# H_Bridge.net
KiCad netlist of a schematic drawn in Altium Designer
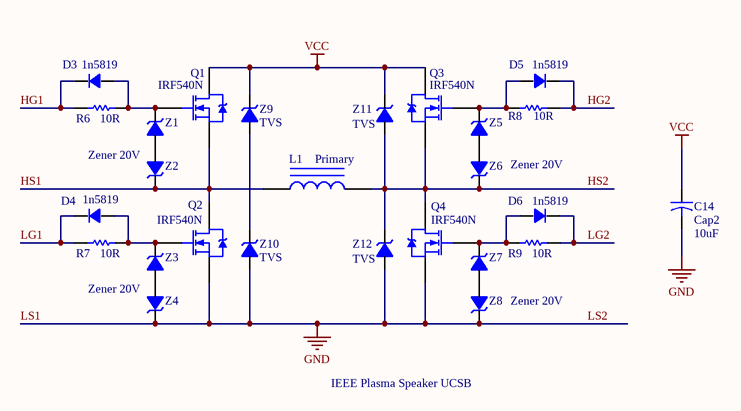
[diagram p0: H Bridge.SchDoc]

(export (version "E")
  (design (tool "Eeschema 10.0.6"))
  (components
    (comp (ref "C14")
      (value "Cap2")
      (footprint "CAPR5-4X5")
      (description "Capacitor")
      (fields (field (name "ALTIUM_VALUE") "10uF") (field (name "PUBLISHER") "Altium Limited"))
      (libsource (lib "Miscellaneous Devices") (part "Cap2"))
    )
    (comp (ref "D3")
      (value "1n5819")
      (footprint "DIODE-0.7")
      (description "Zener Diode")
      (fields (field (name "PUBLISHER") "Altium Limited"))
      (libsource (lib "Miscellaneous Devices") (part "Diode S"))
    )
    (comp (ref "D4")
      (value "1n5819")
      (footprint "DIODE-0.7")
      (description "Zener Diode")
      (fields (field (name "PUBLISHER") "Altium Limited"))
      (libsource (lib "Miscellaneous Devices") (part "Diode S"))
    )
    (comp (ref "D5")
      (value "1n5819")
      (footprint "DIODE-0.7")
      (description "Zener Diode")
      (fields (field (name "PUBLISHER") "Altium Limited"))
      (libsource (lib "Miscellaneous Devices") (part "Diode S"))
    )
    (comp (ref "D6")
      (value "1n5819")
      (footprint "DIODE-0.7")
      (description "Zener Diode")
      (fields (field (name "PUBLISHER") "Altium Limited"))
      (libsource (lib "Miscellaneous Devices") (part "Diode S"))
    )
    (comp (ref "L1")
      (value "Primary")
      (footprint "AXIAL-0.9")
      (description "Magnetic-Core Inductor")
      (fields (field (name "Comment") "Inductor Iron") (field (name "PUBLISHER") "Altium Limited"))
      (libsource (lib "Miscellaneous Devices") (part "Inductor Iron"))
    )
    (comp (ref "Q1")
      (value "IRF540N")
      (footprint "TO-220AB")
      (description "N-Channel Power MOSFET")
      (fields (field (name "PUBLISHER") "Altium Limited"))
      (libsource (lib "Transistor") (part "IRF540N"))
    )
    (comp (ref "Q2")
      (value "IRF540N")
      (footprint "TO-220AB")
      (description "N-Channel Power MOSFET")
      (fields (field (name "PUBLISHER") "Altium Limited"))
      (libsource (lib "Transistor") (part "IRF540N"))
    )
    (comp (ref "Q3")
      (value "IRF540N")
      (footprint "TO-220AB")
      (description "N-Channel Power MOSFET")
      (fields (field (name "PUBLISHER") "Altium Limited"))
      (libsource (lib "Transistor") (part "IRF540N"))
    )
    (comp (ref "Q4")
      (value "IRF540N")
      (footprint "TO-220AB")
      (description "N-Channel Power MOSFET")
      (fields (field (name "PUBLISHER") "Altium Limited"))
      (libsource (lib "Transistor") (part "IRF540N"))
    )
    (comp (ref "R6")
      (value "10R")
      (footprint "AXIAL-0.3")
      (description "Resistor")
      (fields (field (name "Comment") "0805") (field (name "PUBLISHER") "Altium Limited"))
      (libsource (lib "Miscellaneous Devices") (part "Res1"))
    )
    (comp (ref "R7")
      (value "10R")
      (footprint "AXIAL-0.3")
      (description "Resistor")
      (fields (field (name "Comment") "0805") (field (name "PUBLISHER") "Altium Limited"))
      (libsource (lib "Miscellaneous Devices") (part "Res1"))
    )
    (comp (ref "R8")
      (value "10R")
      (footprint "AXIAL-0.3")
      (description "Resistor")
      (fields (field (name "Comment") "0805") (field (name "PUBLISHER") "Altium Limited"))
      (libsource (lib "Miscellaneous Devices") (part "Res1"))
    )
    (comp (ref "R9")
      (value "10R")
      (footprint "AXIAL-0.3")
      (description "Resistor")
      (fields (field (name "Comment") "0805") (field (name "PUBLISHER") "Altium Limited"))
      (libsource (lib "Miscellaneous Devices") (part "Res1"))
    )
    (comp (ref "Z1")
      (value "Zener 20V")
      (footprint "DIODE-0.7")
      (description "Zener Diode")
      (fields (field (name "PUBLISHER") "Altium Limited"))
      (libsource (lib "Miscellaneous Devices") (part "Zener"))
    )
    (comp (ref "Z2")
      (value "Zener")
      (footprint "DIODE-0.7")
      (description "Zener Diode")
      (fields (field (name "PUBLISHER") "Altium Limited"))
      (libsource (lib "Miscellaneous Devices") (part "Zener"))
    )
    (comp (ref "Z3")
      (value "Zener 20V")
      (footprint "DIODE-0.7")
      (description "Zener Diode")
      (fields (field (name "PUBLISHER") "Altium Limited"))
      (libsource (lib "Miscellaneous Devices") (part "Zener"))
    )
    (comp (ref "Z4")
      (value "Zener")
      (footprint "DIODE-0.7")
      (description "Zener Diode")
      (fields (field (name "PUBLISHER") "Altium Limited"))
      (libsource (lib "Miscellaneous Devices") (part "Zener"))
    )
    (comp (ref "Z5")
      (value "Zener 20V")
      (footprint "DIODE-0.7")
      (description "Zener Diode")
      (fields (field (name "PUBLISHER") "Altium Limited"))
      (libsource (lib "Miscellaneous Devices") (part "Zener"))
    )
    (comp (ref "Z6")
      (value "Zener")
      (footprint "DIODE-0.7")
      (description "Zener Diode")
      (fields (field (name "PUBLISHER") "Altium Limited"))
      (libsource (lib "Miscellaneous Devices") (part "Zener"))
    )
    (comp (ref "Z7")
      (value "Zener 20V")
      (footprint "DIODE-0.7")
      (description "Zener Diode")
      (fields (field (name "PUBLISHER") "Altium Limited"))
      (libsource (lib "Miscellaneous Devices") (part "Zener"))
    )
    (comp (ref "Z8")
      (value "Zener")
      (footprint "DIODE-0.7")
      (description "Zener Diode")
      (fields (field (name "PUBLISHER") "Altium Limited"))
      (libsource (lib "Miscellaneous Devices") (part "Zener"))
    )
    (comp (ref "Z9")
      (value "TVS")
      (footprint "DIODE-0.7")
      (description "Zener Diode")
      (fields (field (name "PUBLISHER") "Altium Limited"))
      (libsource (lib "Miscellaneous Devices") (part "Zener"))
    )
    (comp (ref "Z10")
      (value "TVS")
      (footprint "DIODE-0.7")
      (description "Zener Diode")
      (fields (field (name "PUBLISHER") "Altium Limited"))
      (libsource (lib "Miscellaneous Devices") (part "Zener"))
    )
    (comp (ref "Z11")
      (value "TVS")
      (footprint "DIODE-0.7")
      (description "Zener Diode")
      (fields (field (name "PUBLISHER") "Altium Limited"))
      (libsource (lib "Miscellaneous Devices") (part "Zener"))
    )
    (comp (ref "Z12")
      (value "TVS")
      (footprint "DIODE-0.7")
      (description "Zener Diode")
      (fields (field (name "PUBLISHER") "Altium Limited"))
      (libsource (lib "Miscellaneous Devices") (part "Zener"))
    )
  )
  (nets
    (net (code "1") (name "/HG1") (class "Default")
      (node (ref "D3") (pin "2") (pinfunction "2_2") (pintype "passive"))
      (node (ref "R6") (pin "2") (pinfunction "2_2") (pintype "passive"))
    )
    (net (code "2") (name "/HG2") (class "Default")
      (node (ref "D5") (pin "2") (pinfunction "2_2") (pintype "passive"))
      (node (ref "R8") (pin "1") (pinfunction "1_1") (pintype "passive"))
    )
    (net (code "3") (name "/HS1") (class "Default")
      (node (ref "L1") (pin "1") (pinfunction "1_1") (pintype "passive"))
      (node (ref "Q1") (pin "3") (pinfunction "S_3") (pintype "passive"))
      (node (ref "Q2") (pin "2") (pinfunction "D_2") (pintype "passive"))
      (node (ref "Z2") (pin "2") (pinfunction "2_2") (pintype "passive"))
    )
    (net (code "4") (name "/HS2") (class "Default")
      (node (ref "L1") (pin "2") (pinfunction "2_2") (pintype "passive"))
      (node (ref "Q3") (pin "3") (pinfunction "S_3") (pintype "passive"))
      (node (ref "Q4") (pin "2") (pinfunction "D_2") (pintype "passive"))
      (node (ref "Z11") (pin "1") (pinfunction "1_1") (pintype "passive"))
      (node (ref "Z12") (pin "2") (pinfunction "2_2") (pintype "passive"))
      (node (ref "Z6") (pin "2") (pinfunction "2_2") (pintype "passive"))
    )
    (net (code "5") (name "/LG1") (class "Default")
      (node (ref "D4") (pin "2") (pinfunction "2_2") (pintype "passive"))
      (node (ref "R7") (pin "2") (pinfunction "2_2") (pintype "passive"))
    )
    (net (code "6") (name "/LG2") (class "Default")
      (node (ref "D6") (pin "2") (pinfunction "2_2") (pintype "passive"))
      (node (ref "R9") (pin "1") (pinfunction "1_1") (pintype "passive"))
    )
    (net (code "7") (name "GND") (class "Default")
      (node (ref "C14") (pin "2") (pinfunction "2_2") (pintype "passive"))
      (node (ref "Q2") (pin "3") (pinfunction "S_3") (pintype "passive"))
      (node (ref "Q4") (pin "3") (pinfunction "S_3") (pintype "passive"))
      (node (ref "Z10") (pin "1") (pinfunction "1_1") (pintype "passive"))
      (node (ref "Z12") (pin "1") (pinfunction "1_1") (pintype "passive"))
      (node (ref "Z4") (pin "2") (pinfunction "2_2") (pintype "passive"))
      (node (ref "Z8") (pin "2") (pinfunction "2_2") (pintype "passive"))
    )
    (net (code "8") (name "Net-(Q1-G)") (class "Default")
      (node (ref "D3") (pin "1") (pinfunction "1_1") (pintype "passive"))
      (node (ref "Q1") (pin "1") (pinfunction "G_1") (pintype "passive"))
      (node (ref "R6") (pin "1") (pinfunction "1_1") (pintype "passive"))
      (node (ref "Z1") (pin "2") (pinfunction "2_2") (pintype "passive"))
    )
    (net (code "9") (name "Net-(Q2-G)") (class "Default")
      (node (ref "D4") (pin "1") (pinfunction "1_1") (pintype "passive"))
      (node (ref "Q2") (pin "1") (pinfunction "G_1") (pintype "passive"))
      (node (ref "R7") (pin "1") (pinfunction "1_1") (pintype "passive"))
      (node (ref "Z3") (pin "2") (pinfunction "2_2") (pintype "passive"))
    )
    (net (code "10") (name "Net-(Q3-G)") (class "Default")
      (node (ref "D5") (pin "1") (pinfunction "1_1") (pintype "passive"))
      (node (ref "Q3") (pin "1") (pinfunction "G_1") (pintype "passive"))
      (node (ref "R8") (pin "2") (pinfunction "2_2") (pintype "passive"))
      (node (ref "Z5") (pin "2") (pinfunction "2_2") (pintype "passive"))
    )
    (net (code "11") (name "Net-(Q4-G)") (class "Default")
      (node (ref "D6") (pin "1") (pinfunction "1_1") (pintype "passive"))
      (node (ref "Q4") (pin "1") (pinfunction "G_1") (pintype "passive"))
      (node (ref "R9") (pin "2") (pinfunction "2_2") (pintype "passive"))
      (node (ref "Z7") (pin "2") (pinfunction "2_2") (pintype "passive"))
    )
    (net (code "12") (name "Net-(Z1-Pad1)") (class "Default")
      (node (ref "Z1") (pin "1") (pinfunction "1_1") (pintype "passive"))
      (node (ref "Z2") (pin "1") (pinfunction "1_1") (pintype "passive"))
    )
    (net (code "13") (name "Net-(Z3-Pad1)") (class "Default")
      (node (ref "Z3") (pin "1") (pinfunction "1_1") (pintype "passive"))
      (node (ref "Z4") (pin "1") (pinfunction "1_1") (pintype "passive"))
    )
    (net (code "14") (name "Net-(Z5-Pad1)") (class "Default")
      (node (ref "Z5") (pin "1") (pinfunction "1_1") (pintype "passive"))
      (node (ref "Z6") (pin "1") (pinfunction "1_1") (pintype "passive"))
    )
    (net (code "15") (name "Net-(Z7-Pad1)") (class "Default")
      (node (ref "Z7") (pin "1") (pinfunction "1_1") (pintype "passive"))
      (node (ref "Z8") (pin "1") (pinfunction "1_1") (pintype "passive"))
    )
    (net (code "16") (name "Net-(Z10-Pad2)") (class "Default")
      (node (ref "Z10") (pin "2") (pinfunction "2_2") (pintype "passive"))
      (node (ref "Z9") (pin "1") (pinfunction "1_1") (pintype "passive"))
    )
    (net (code "17") (name "VCC") (class "Default")
      (node (ref "C14") (pin "1") (pinfunction "1_1") (pintype "passive"))
      (node (ref "Q1") (pin "2") (pinfunction "D_2") (pintype "passive"))
      (node (ref "Q3") (pin "2") (pinfunction "D_2") (pintype "passive"))
      (node (ref "Z11") (pin "2") (pinfunction "2_2") (pintype "passive"))
      (node (ref "Z9") (pin "2") (pinfunction "2_2") (pintype "passive"))
    )
  )
)
